# solenoid_valve.net
KiCad netlist of a schematic drawn in EAGLE
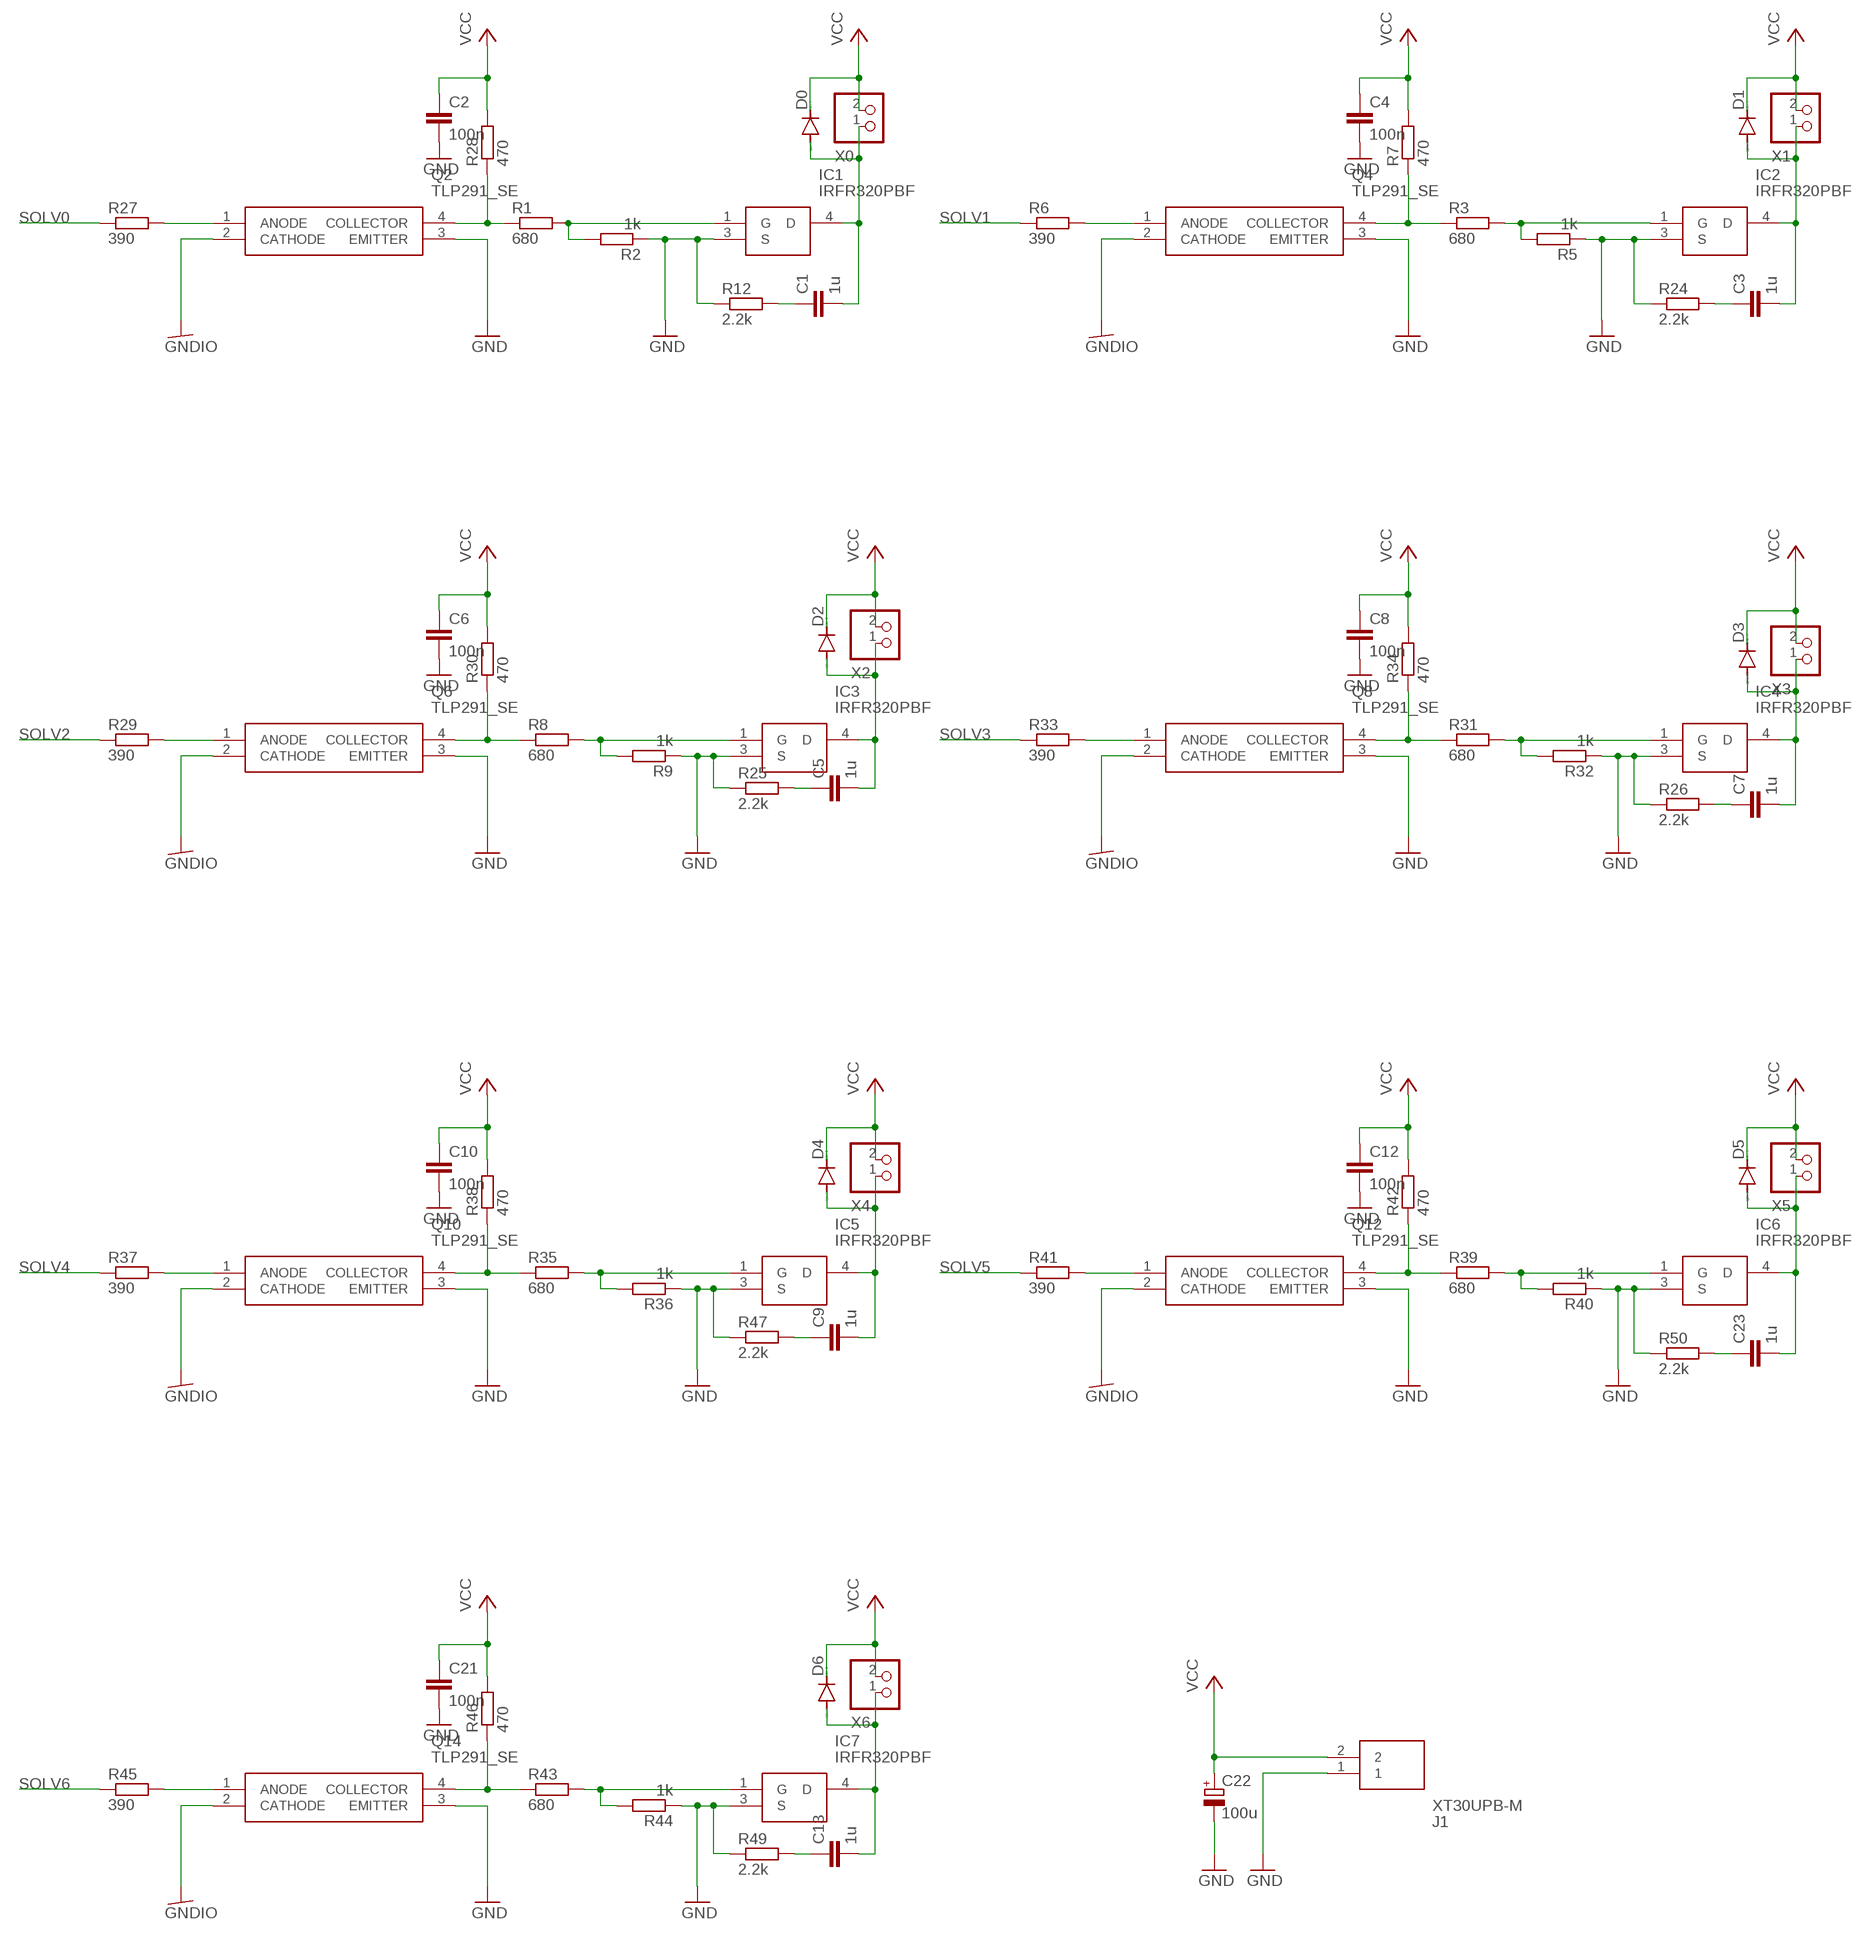
[diagram p0: schematic, sheet 1]
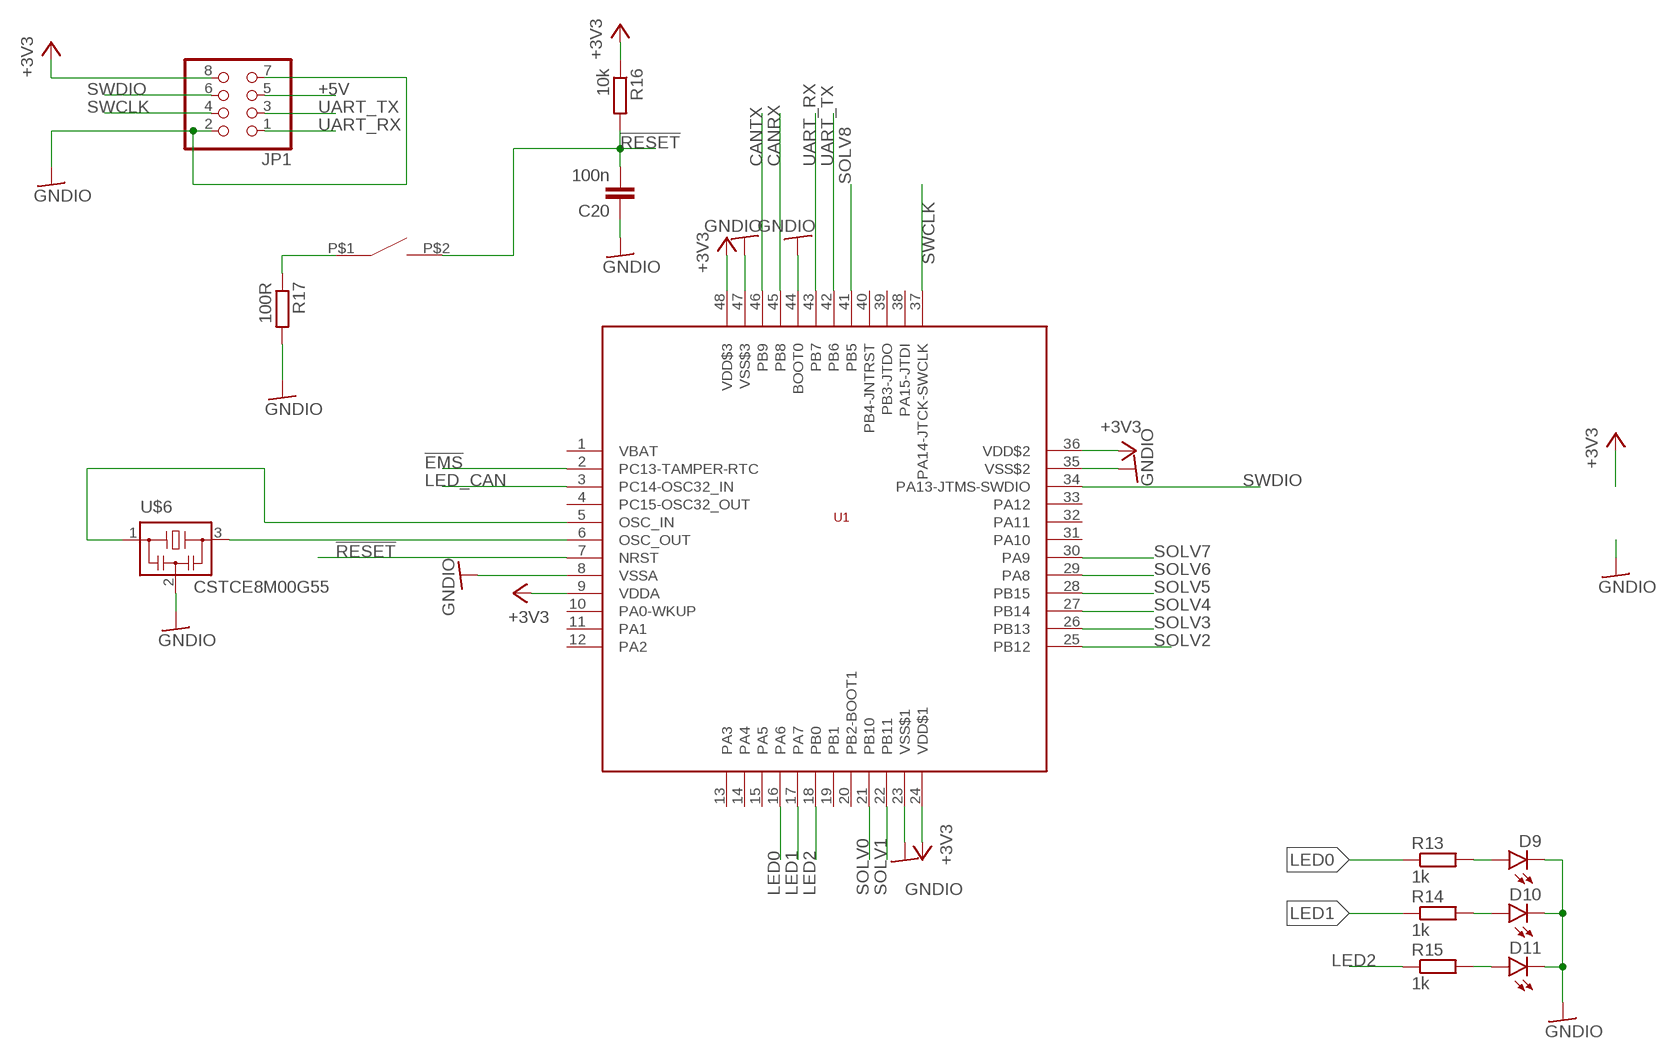
[diagram p1: schematic, sheet 2]
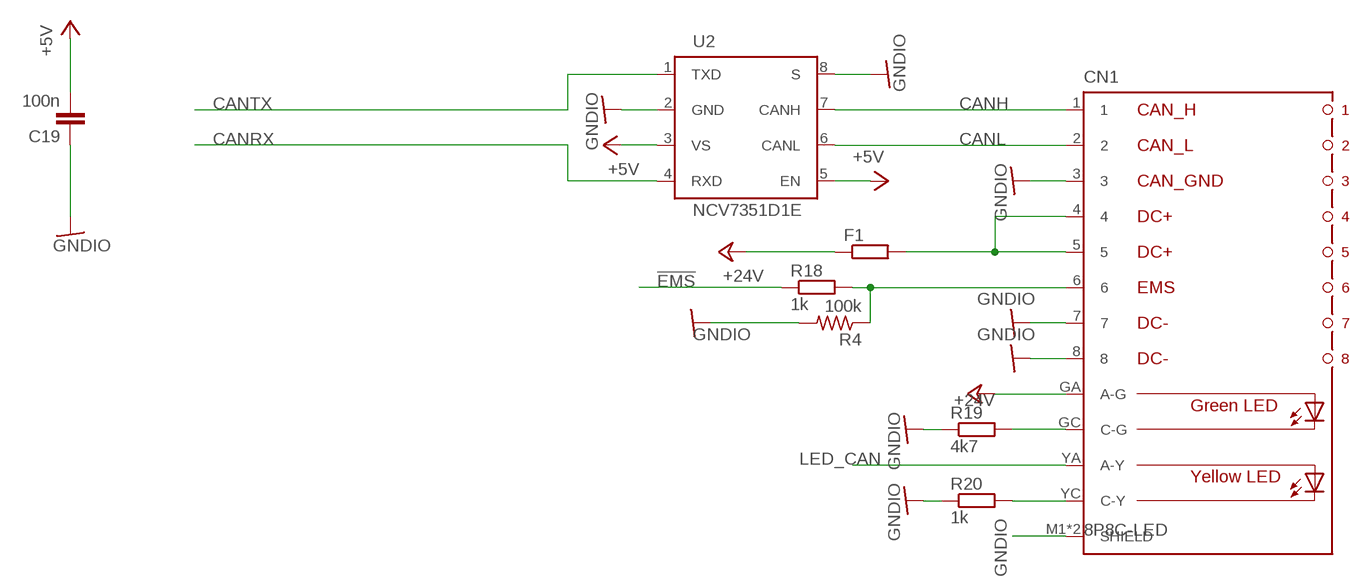
[diagram p2: schematic, sheet 3]
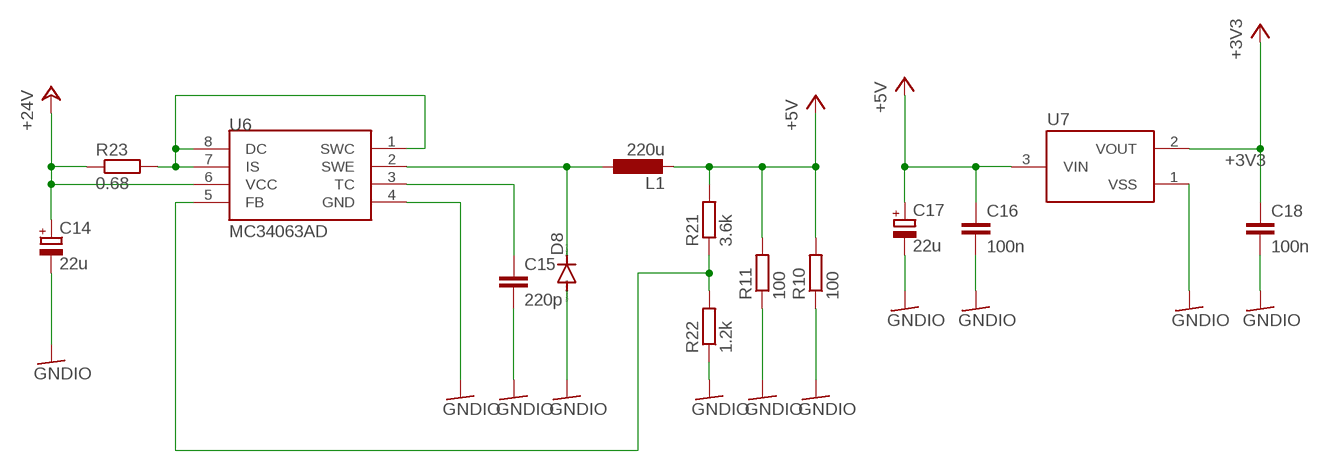
[diagram p3: schematic, sheet 4]

(export (version "E")
  (design (tool "Eeschema 10.0.6"))
  (components
    (comp (ref "C1")
      (value "1u")
      (footprint "eagle-import:C0603")
      (libsource (lib "eagle-import") (part "rcl_334_C-EUC0603"))
    )
    (comp (ref "C2")
      (value "100n")
      (footprint "eagle-import:C0603")
      (libsource (lib "eagle-import") (part "rcl_334_C-EUC0603"))
    )
    (comp (ref "C3")
      (value "1u")
      (footprint "eagle-import:C0603")
      (libsource (lib "eagle-import") (part "rcl_334_C-EUC0603"))
    )
    (comp (ref "C4")
      (value "100n")
      (footprint "eagle-import:C0603")
      (libsource (lib "eagle-import") (part "rcl_334_C-EUC0603"))
    )
    (comp (ref "C5")
      (value "1u")
      (footprint "eagle-import:C0603")
      (libsource (lib "eagle-import") (part "rcl_334_C-EUC0603"))
    )
    (comp (ref "C6")
      (value "100n")
      (footprint "eagle-import:C0603")
      (libsource (lib "eagle-import") (part "rcl_334_C-EUC0603"))
    )
    (comp (ref "C7")
      (value "1u")
      (footprint "eagle-import:C0603")
      (libsource (lib "eagle-import") (part "rcl_334_C-EUC0603"))
    )
    (comp (ref "C8")
      (value "100n")
      (footprint "eagle-import:C0603")
      (libsource (lib "eagle-import") (part "rcl_334_C-EUC0603"))
    )
    (comp (ref "C9")
      (value "1u")
      (footprint "eagle-import:C0603")
      (libsource (lib "eagle-import") (part "rcl_334_C-EUC0603"))
    )
    (comp (ref "C10")
      (value "100n")
      (footprint "eagle-import:C0603")
      (libsource (lib "eagle-import") (part "rcl_334_C-EUC0603"))
    )
    (comp (ref "C12")
      (value "100n")
      (footprint "eagle-import:C0603")
      (libsource (lib "eagle-import") (part "rcl_334_C-EUC0603"))
    )
    (comp (ref "C13")
      (value "1u")
      (footprint "eagle-import:C0603")
      (libsource (lib "eagle-import") (part "rcl_334_C-EUC0603"))
    )
    (comp (ref "C21")
      (value "100n")
      (footprint "eagle-import:C0603")
      (libsource (lib "eagle-import") (part "rcl_334_C-EUC0603"))
    )
    (comp (ref "C22")
      (value "100u")
      (footprint "eagle-import:E2-5")
      (libsource (lib "eagle-import") (part "rcl_334_CPOL-EUE2-5"))
    )
    (comp (ref "C23")
      (value "1u")
      (footprint "eagle-import:C0603")
      (libsource (lib "eagle-import") (part "rcl_334_C-EUC0603"))
    )
    (comp (ref "D0")
      (value "DIODE-SOD123")
      (footprint "eagle-import:SOD123")
      (libsource (lib "eagle-import") (part "DIODE-SOD123"))
    )
    (comp (ref "D1")
      (value "DIODE-SOD123")
      (footprint "eagle-import:SOD123")
      (libsource (lib "eagle-import") (part "DIODE-SOD123"))
    )
    (comp (ref "D2")
      (value "DIODE-SOD123")
      (footprint "eagle-import:SOD123")
      (libsource (lib "eagle-import") (part "DIODE-SOD123"))
    )
    (comp (ref "D3")
      (value "DIODE-SOD123")
      (footprint "eagle-import:SOD123")
      (libsource (lib "eagle-import") (part "DIODE-SOD123"))
    )
    (comp (ref "D4")
      (value "DIODE-SOD123")
      (footprint "eagle-import:SOD123")
      (libsource (lib "eagle-import") (part "DIODE-SOD123"))
    )
    (comp (ref "D5")
      (value "DIODE-SOD123")
      (footprint "eagle-import:SOD123")
      (libsource (lib "eagle-import") (part "DIODE-SOD123"))
    )
    (comp (ref "D6")
      (value "DIODE-SOD123")
      (footprint "eagle-import:SOD123")
      (libsource (lib "eagle-import") (part "DIODE-SOD123"))
    )
    (comp (ref "IC1")
      (value "IRFR320PBF")
      (footprint "eagle-import:TO228P990X238-3N")
      (fields (field (name "MOUSER_PART_NUMBER") "844-IRFR320PBF"))
      (libsource (lib "eagle-import") (part "IRFR320PBF"))
    )
    (comp (ref "IC2")
      (value "IRFR320PBF")
      (footprint "eagle-import:TO228P990X238-3N")
      (fields (field (name "MOUSER_PART_NUMBER") "844-IRFR320PBF"))
      (libsource (lib "eagle-import") (part "IRFR320PBF"))
    )
    (comp (ref "IC3")
      (value "IRFR320PBF")
      (footprint "eagle-import:TO228P990X238-3N")
      (fields (field (name "MOUSER_PART_NUMBER") "844-IRFR320PBF"))
      (libsource (lib "eagle-import") (part "IRFR320PBF"))
    )
    (comp (ref "IC4")
      (value "IRFR320PBF")
      (footprint "eagle-import:TO228P990X238-3N")
      (fields (field (name "MOUSER_PART_NUMBER") "844-IRFR320PBF"))
      (libsource (lib "eagle-import") (part "IRFR320PBF"))
    )
    (comp (ref "IC5")
      (value "IRFR320PBF")
      (footprint "eagle-import:TO228P990X238-3N")
      (fields (field (name "MOUSER_PART_NUMBER") "844-IRFR320PBF"))
      (libsource (lib "eagle-import") (part "IRFR320PBF"))
    )
    (comp (ref "IC6")
      (value "IRFR320PBF")
      (footprint "eagle-import:TO228P990X238-3N")
      (fields (field (name "MOUSER_PART_NUMBER") "844-IRFR320PBF"))
      (libsource (lib "eagle-import") (part "IRFR320PBF"))
    )
    (comp (ref "IC7")
      (value "IRFR320PBF")
      (footprint "eagle-import:TO228P990X238-3N")
      (fields (field (name "MOUSER_PART_NUMBER") "844-IRFR320PBF"))
      (libsource (lib "eagle-import") (part "IRFR320PBF"))
    )
    (comp (ref "J1")
      (value "XT30UPB-M")
      (footprint "eagle-import:SHDR2W160P0X500_1X2_1020X520X1")
      (libsource (lib "eagle-import") (part "XT30UPB-M"))
    )
    (comp (ref "Q2")
      (value "TLP291_SE")
      (footprint "eagle-import:SOIC127P700X230-4N")
      (fields
        (field (name "ARROW_PART_NUMBER") "TLP291(SE")
        (field (name "MOUSER_PART_NUMBER") "757-TLP291SE")
      )
      (libsource (lib "eagle-import") (part "TLP291_SE"))
    )
    (comp (ref "Q4")
      (value "TLP291_SE")
      (footprint "eagle-import:SOIC127P700X230-4N")
      (fields
        (field (name "ARROW_PART_NUMBER") "TLP291(SE")
        (field (name "MOUSER_PART_NUMBER") "757-TLP291SE")
      )
      (libsource (lib "eagle-import") (part "TLP291_SE"))
    )
    (comp (ref "Q6")
      (value "TLP291_SE")
      (footprint "eagle-import:SOIC127P700X230-4N")
      (fields
        (field (name "ARROW_PART_NUMBER") "TLP291(SE")
        (field (name "MOUSER_PART_NUMBER") "757-TLP291SE")
      )
      (libsource (lib "eagle-import") (part "TLP291_SE"))
    )
    (comp (ref "Q8")
      (value "TLP291_SE")
      (footprint "eagle-import:SOIC127P700X230-4N")
      (fields
        (field (name "ARROW_PART_NUMBER") "TLP291(SE")
        (field (name "MOUSER_PART_NUMBER") "757-TLP291SE")
      )
      (libsource (lib "eagle-import") (part "TLP291_SE"))
    )
    (comp (ref "Q10")
      (value "TLP291_SE")
      (footprint "eagle-import:SOIC127P700X230-4N")
      (fields
        (field (name "ARROW_PART_NUMBER") "TLP291(SE")
        (field (name "MOUSER_PART_NUMBER") "757-TLP291SE")
      )
      (libsource (lib "eagle-import") (part "TLP291_SE"))
    )
    (comp (ref "Q12")
      (value "TLP291_SE")
      (footprint "eagle-import:SOIC127P700X230-4N")
      (fields
        (field (name "ARROW_PART_NUMBER") "TLP291(SE")
        (field (name "MOUSER_PART_NUMBER") "757-TLP291SE")
      )
      (libsource (lib "eagle-import") (part "TLP291_SE"))
    )
    (comp (ref "Q14")
      (value "TLP291_SE")
      (footprint "eagle-import:SOIC127P700X230-4N")
      (fields
        (field (name "ARROW_PART_NUMBER") "TLP291(SE")
        (field (name "MOUSER_PART_NUMBER") "757-TLP291SE")
      )
      (libsource (lib "eagle-import") (part "TLP291_SE"))
    )
    (comp (ref "R1")
      (value "680")
      (footprint "eagle-import:R0603")
      (libsource (lib "eagle-import") (part "rcl_334_R-EU_R0603"))
    )
    (comp (ref "R2")
      (value "1k")
      (footprint "eagle-import:R0603")
      (libsource (lib "eagle-import") (part "rcl_334_R-EU_R0603"))
    )
    (comp (ref "R3")
      (value "680")
      (footprint "eagle-import:R0603")
      (libsource (lib "eagle-import") (part "rcl_334_R-EU_R0603"))
    )
    (comp (ref "R5")
      (value "1k")
      (footprint "eagle-import:R0603")
      (libsource (lib "eagle-import") (part "rcl_334_R-EU_R0603"))
    )
    (comp (ref "R6")
      (value "390")
      (footprint "eagle-import:R0603")
      (libsource (lib "eagle-import") (part "rcl_334_R-EU_R0603"))
    )
    (comp (ref "R7")
      (value "470")
      (footprint "eagle-import:R0603")
      (libsource (lib "eagle-import") (part "rcl_334_R-EU_R0603"))
    )
    (comp (ref "R8")
      (value "680")
      (footprint "eagle-import:R0603")
      (libsource (lib "eagle-import") (part "rcl_334_R-EU_R0603"))
    )
    (comp (ref "R9")
      (value "1k")
      (footprint "eagle-import:R0603")
      (libsource (lib "eagle-import") (part "rcl_334_R-EU_R0603"))
    )
    (comp (ref "R12")
      (value "2.2k")
      (footprint "eagle-import:R0603")
      (libsource (lib "eagle-import") (part "rcl_334_R-EU_R0603"))
    )
    (comp (ref "R24")
      (value "2.2k")
      (footprint "eagle-import:R0603")
      (libsource (lib "eagle-import") (part "rcl_334_R-EU_R0603"))
    )
    (comp (ref "R25")
      (value "2.2k")
      (footprint "eagle-import:R0603")
      (libsource (lib "eagle-import") (part "rcl_334_R-EU_R0603"))
    )
    (comp (ref "R26")
      (value "2.2k")
      (footprint "eagle-import:R0603")
      (libsource (lib "eagle-import") (part "rcl_334_R-EU_R0603"))
    )
    (comp (ref "R27")
      (value "390")
      (footprint "eagle-import:R0603")
      (libsource (lib "eagle-import") (part "rcl_334_R-EU_R0603"))
    )
    (comp (ref "R28")
      (value "470")
      (footprint "eagle-import:R0603")
      (libsource (lib "eagle-import") (part "rcl_334_R-EU_R0603"))
    )
    (comp (ref "R29")
      (value "390")
      (footprint "eagle-import:R0603")
      (libsource (lib "eagle-import") (part "rcl_334_R-EU_R0603"))
    )
    (comp (ref "R30")
      (value "470")
      (footprint "eagle-import:R0603")
      (libsource (lib "eagle-import") (part "rcl_334_R-EU_R0603"))
    )
    (comp (ref "R31")
      (value "680")
      (footprint "eagle-import:R0603")
      (libsource (lib "eagle-import") (part "rcl_334_R-EU_R0603"))
    )
    (comp (ref "R32")
      (value "1k")
      (footprint "eagle-import:R0603")
      (libsource (lib "eagle-import") (part "rcl_334_R-EU_R0603"))
    )
    (comp (ref "R33")
      (value "390")
      (footprint "eagle-import:R0603")
      (libsource (lib "eagle-import") (part "rcl_334_R-EU_R0603"))
    )
    (comp (ref "R34")
      (value "470")
      (footprint "eagle-import:R0603")
      (libsource (lib "eagle-import") (part "rcl_334_R-EU_R0603"))
    )
    (comp (ref "R35")
      (value "680")
      (footprint "eagle-import:R0603")
      (libsource (lib "eagle-import") (part "rcl_334_R-EU_R0603"))
    )
    (comp (ref "R36")
      (value "1k")
      (footprint "eagle-import:R0603")
      (libsource (lib "eagle-import") (part "rcl_334_R-EU_R0603"))
    )
    (comp (ref "R37")
      (value "390")
      (footprint "eagle-import:R0603")
      (libsource (lib "eagle-import") (part "rcl_334_R-EU_R0603"))
    )
    (comp (ref "R38")
      (value "470")
      (footprint "eagle-import:R0603")
      (libsource (lib "eagle-import") (part "rcl_334_R-EU_R0603"))
    )
    (comp (ref "R39")
      (value "680")
      (footprint "eagle-import:R0603")
      (libsource (lib "eagle-import") (part "rcl_334_R-EU_R0603"))
    )
    (comp (ref "R40")
      (value "1k")
      (footprint "eagle-import:R0603")
      (libsource (lib "eagle-import") (part "rcl_334_R-EU_R0603"))
    )
    (comp (ref "R41")
      (value "390")
      (footprint "eagle-import:R0603")
      (libsource (lib "eagle-import") (part "rcl_334_R-EU_R0603"))
    )
    (comp (ref "R42")
      (value "470")
      (footprint "eagle-import:R0603")
      (libsource (lib "eagle-import") (part "rcl_334_R-EU_R0603"))
    )
    (comp (ref "R43")
      (value "680")
      (footprint "eagle-import:R0603")
      (libsource (lib "eagle-import") (part "rcl_334_R-EU_R0603"))
    )
    (comp (ref "R44")
      (value "1k")
      (footprint "eagle-import:R0603")
      (libsource (lib "eagle-import") (part "rcl_334_R-EU_R0603"))
    )
    (comp (ref "R45")
      (value "390")
      (footprint "eagle-import:R0603")
      (libsource (lib "eagle-import") (part "rcl_334_R-EU_R0603"))
    )
    (comp (ref "R46")
      (value "470")
      (footprint "eagle-import:R0603")
      (libsource (lib "eagle-import") (part "rcl_334_R-EU_R0603"))
    )
    (comp (ref "R47")
      (value "2.2k")
      (footprint "eagle-import:R0603")
      (libsource (lib "eagle-import") (part "rcl_334_R-EU_R0603"))
    )
    (comp (ref "R49")
      (value "2.2k")
      (footprint "eagle-import:R0603")
      (libsource (lib "eagle-import") (part "rcl_334_R-EU_R0603"))
    )
    (comp (ref "R50")
      (value "2.2k")
      (footprint "eagle-import:R0603")
      (libsource (lib "eagle-import") (part "rcl_334_R-EU_R0603"))
    )
    (comp (ref "X0")
      (value "S2B-XASK-1")
      (footprint "eagle-import:S2B-XASK-1")
      (libsource (lib "eagle-import") (part "S2B-XASK-1"))
    )
    (comp (ref "X1")
      (value "S2B-XASK-1")
      (footprint "eagle-import:S2B-XASK-1")
      (libsource (lib "eagle-import") (part "S2B-XASK-1"))
    )
    (comp (ref "X2")
      (value "S2B-XASK-1")
      (footprint "eagle-import:S2B-XASK-1")
      (libsource (lib "eagle-import") (part "S2B-XASK-1"))
    )
    (comp (ref "X3")
      (value "S2B-XASK-1")
      (footprint "eagle-import:S2B-XASK-1")
      (libsource (lib "eagle-import") (part "S2B-XASK-1"))
    )
    (comp (ref "X4")
      (value "S2B-XASK-1")
      (footprint "eagle-import:S2B-XASK-1")
      (libsource (lib "eagle-import") (part "S2B-XASK-1"))
    )
    (comp (ref "X5")
      (value "S2B-XASK-1")
      (footprint "eagle-import:S2B-XASK-1")
      (libsource (lib "eagle-import") (part "S2B-XASK-1"))
    )
    (comp (ref "X6")
      (value "S2B-XASK-1")
      (footprint "eagle-import:S2B-XASK-1")
      (libsource (lib "eagle-import") (part "S2B-XASK-1"))
    )
    (comp (ref "C14")
      (value "22u")
      (footprint "eagle-import:E2-5")
      (libsource (lib "eagle-import") (part "CPOL-EUE2-5"))
    )
    (comp (ref "C15")
      (value "220p")
      (footprint "eagle-import:C0603")
      (libsource (lib "eagle-import") (part "rcl_334_C-EUC0603"))
    )
    (comp (ref "C16")
      (value "100n")
      (footprint "eagle-import:C0603")
      (libsource (lib "eagle-import") (part "C-EUC0603"))
    )
    (comp (ref "C17")
      (value "22u")
      (footprint "eagle-import:E2-5")
      (libsource (lib "eagle-import") (part "CPOL-EUE2-5"))
    )
    (comp (ref "C18")
      (value "100n")
      (footprint "eagle-import:C0603")
      (libsource (lib "eagle-import") (part "C-EUC0603"))
    )
    (comp (ref "D8")
      (value "DIODE-SOD123")
      (footprint "eagle-import:SOD123")
      (libsource (lib "eagle-import") (part "DIODE-SOD123"))
    )
    (comp (ref "L1")
      (value "220u")
      (footprint "eagle-import:L5852")
      (libsource (lib "eagle-import") (part "L5852"))
    )
    (comp (ref "R10")
      (value "100")
      (footprint "eagle-import:R0603")
      (libsource (lib "eagle-import") (part "rcl_334_R-EU_R0603"))
    )
    (comp (ref "R11")
      (value "100")
      (footprint "eagle-import:R0603")
      (libsource (lib "eagle-import") (part "rcl_334_R-EU_R0603"))
    )
    (comp (ref "R21")
      (value "3.6k")
      (footprint "eagle-import:R0603")
      (libsource (lib "eagle-import") (part "rcl_334_R-EU_R0603"))
    )
    (comp (ref "R22")
      (value "1.2k")
      (footprint "eagle-import:R0603")
      (libsource (lib "eagle-import") (part "rcl_334_R-EU_R0603"))
    )
    (comp (ref "R23")
      (value "0.68")
      (footprint "eagle-import:R1206")
      (libsource (lib "eagle-import") (part "rcl_334_R-EU_R1206"))
    )
    (comp (ref "U6")
      (value "MC34063AD")
      (footprint "eagle-import:SOIC8")
      (libsource (lib "eagle-import") (part "MC34063AD"))
    )
    (comp (ref "U7")
      (value "XC6206")
      (footprint "eagle-import:SOT95P240X110-3")
      (libsource (lib "eagle-import") (part "XC6206"))
    )
    (comp (ref "C20")
      (value "100n")
      (footprint "eagle-import:C0603")
      (libsource (lib "eagle-import") (part "C-EUC0603"))
    )
    (comp (ref "D9")
      (value "LEDCHIPLED_0805")
      (footprint "eagle-import:CHIPLED_0805")
      (libsource (lib "eagle-import") (part "LEDCHIPLED_0805"))
    )
    (comp (ref "D10")
      (value "LEDCHIPLED_0805")
      (footprint "eagle-import:CHIPLED_0805")
      (libsource (lib "eagle-import") (part "LEDCHIPLED_0805"))
    )
    (comp (ref "D11")
      (value "LEDCHIPLED_0805")
      (footprint "eagle-import:CHIPLED_0805")
      (libsource (lib "eagle-import") (part "LEDCHIPLED_0805"))
    )
    (comp (ref "JP1")
      (value "PINHD-2X4")
      (footprint "eagle-import:2X04")
      (libsource (lib "eagle-import") (part "PINHD-2X4"))
    )
    (comp (ref "R13")
      (value "1k")
      (footprint "eagle-import:R0603")
      (libsource (lib "eagle-import") (part "R-EU_R0603"))
    )
    (comp (ref "R14")
      (value "1k")
      (footprint "eagle-import:R0603")
      (libsource (lib "eagle-import") (part "R-EU_R0603"))
    )
    (comp (ref "R15")
      (value "1k")
      (footprint "eagle-import:R0603")
      (libsource (lib "eagle-import") (part "R-EU_R0603"))
    )
    (comp (ref "R16")
      (value "10k")
      (footprint "eagle-import:R0603")
      (libsource (lib "eagle-import") (part "R-EU_R0603"))
    )
    (comp (ref "R17")
      (value "100R")
      (footprint "eagle-import:R0603")
      (libsource (lib "eagle-import") (part "R-EU_R0603"))
    )
    (comp (ref "SW1")
      (value "SWITCH_TACTILETOP")
      (footprint "eagle-import:SWITCH_TACTILE_3X6")
      (libsource (lib "eagle-import") (part "SWITCH_TACTILETOP"))
    )
    (comp (ref "U$6")
      (value "CSTCE8M00G55")
      (footprint "eagle-import:CSTCE8M00G55")
      (libsource (lib "eagle-import") (part "CSTCE8M00G55"))
    )
    (comp (ref "U1")
      (value "STM32F103C8")
      (footprint "eagle-import:LQFP48")
      (libsource (lib "eagle-import") (part "STM32F103C8"))
    )
    (comp (ref "C19")
      (value "100n")
      (footprint "eagle-import:C0603")
      (libsource (lib "eagle-import") (part "C-EUC0603"))
    )
    (comp (ref "CN1")
      (value "8P8C-LED")
      (footprint "eagle-import:8P8C-LED")
      (libsource (lib "eagle-import") (part "8P8C-LED"))
    )
    (comp (ref "F1")
      (value "R-EU_R1206")
      (footprint "eagle-import:R1206")
      (libsource (lib "eagle-import") (part "rcl_334_R-EU_R1206"))
    )
    (comp (ref "R4")
      (value "100k")
      (footprint "eagle-import:R0603")
      (libsource (lib "eagle-import") (part "R-US_R0603"))
    )
    (comp (ref "R18")
      (value "1k")
      (footprint "eagle-import:R0603")
      (libsource (lib "eagle-import") (part "rcl_334_R-EU_R0603"))
    )
    (comp (ref "R19")
      (value "4k7")
      (footprint "eagle-import:R0603")
      (libsource (lib "eagle-import") (part "rcl_334_R-EU_R0603"))
    )
    (comp (ref "R20")
      (value "1k")
      (footprint "eagle-import:R0603")
      (libsource (lib "eagle-import") (part "rcl_334_R-EU_R0603"))
    )
    (comp (ref "U2")
      (value "NCV7351D1E")
      (footprint "eagle-import:SO08")
      (libsource (lib "eagle-import") (part "NCV7351D1E"))
    )
  )
  (nets
    (net (code "1") (name "+3V3") (class "Default")
      (node (ref "C18") (pin "1") (pinfunction "1_1") (pintype "passive"))
      (node (ref "JP1") (pin "8") (pinfunction "8_8") (pintype "passive"))
      (node (ref "R16") (pin "1") (pinfunction "1_1") (pintype "passive"))
      (node (ref "U1") (pin "24") (pinfunction "VDD$1_24") (pintype "passive"))
      (node (ref "U1") (pin "36") (pinfunction "VDD$2_36") (pintype "passive"))
      (node (ref "U1") (pin "48") (pinfunction "VDD$3_48") (pintype "passive"))
      (node (ref "U1") (pin "9") (pinfunction "VDDA_9") (pintype "bidirectional"))
      (node (ref "U7") (pin "2") (pinfunction "VOUT_2") (pintype "bidirectional"))
    )
    (net (code "2") (name "+5V") (class "Default")
      (node (ref "C16") (pin "1") (pinfunction "1_1") (pintype "passive"))
      (node (ref "C17") (pin "+") (pinfunction "+_+") (pintype "passive"))
      (node (ref "C19") (pin "2") (pinfunction "2_2") (pintype "passive"))
      (node (ref "JP1") (pin "5") (pinfunction "5_5") (pintype "passive"))
      (node (ref "L1") (pin "P$2") (pinfunction "2_P$2") (pintype "passive"))
      (node (ref "R10") (pin "2") (pinfunction "2_2") (pintype "passive"))
      (node (ref "R11") (pin "2") (pinfunction "2_2") (pintype "passive"))
      (node (ref "R21") (pin "2") (pinfunction "2_2") (pintype "passive"))
      (node (ref "U2") (pin "3") (pinfunction "VS_3") (pintype "power_in"))
      (node (ref "U2") (pin "5") (pinfunction "EN_5") (pintype "input"))
      (node (ref "U7") (pin "3") (pinfunction "VIN_3") (pintype "bidirectional"))
    )
    (net (code "3") (name "+24V") (class "Default")
      (node (ref "C14") (pin "+") (pinfunction "+_+") (pintype "passive"))
      (node (ref "CN1") (pin "GA") (pinfunction "A-G_GA") (pintype "passive"))
      (node (ref "F1") (pin "1") (pinfunction "1_1") (pintype "passive"))
      (node (ref "R23") (pin "1") (pinfunction "1_1") (pintype "passive"))
      (node (ref "U6") (pin "6") (pinfunction "VCC_6") (pintype "passive"))
    )
    (net (code "4") (name "CANH") (class "Default")
      (node (ref "CN1") (pin "1") (pinfunction "1_1") (pintype "input"))
      (node (ref "U2") (pin "7") (pinfunction "CANH_7") (pintype "output"))
    )
    (net (code "5") (name "CANL") (class "Default")
      (node (ref "CN1") (pin "2") (pinfunction "2_2") (pintype "input"))
      (node (ref "U2") (pin "6") (pinfunction "CANL_6") (pintype "output"))
    )
    (net (code "6") (name "CANRX") (class "Default")
      (node (ref "U1") (pin "45") (pinfunction "PB8_45") (pintype "bidirectional"))
      (node (ref "U2") (pin "4") (pinfunction "RXD_4") (pintype "output"))
    )
    (net (code "7") (name "CANTX") (class "Default")
      (node (ref "U1") (pin "46") (pinfunction "PB9_46") (pintype "bidirectional"))
      (node (ref "U2") (pin "1") (pinfunction "TXD_1") (pintype "input"))
    )
    (net (code "8") (name "GND") (class "Default")
      (node (ref "C10") (pin "2") (pinfunction "2_2") (pintype "passive"))
      (node (ref "C12") (pin "2") (pinfunction "2_2") (pintype "passive"))
      (node (ref "C2") (pin "2") (pinfunction "2_2") (pintype "passive"))
      (node (ref "C21") (pin "2") (pinfunction "2_2") (pintype "passive"))
      (node (ref "C22") (pin "-") (pinfunction "-_-") (pintype "passive"))
      (node (ref "C4") (pin "2") (pinfunction "2_2") (pintype "passive"))
      (node (ref "C6") (pin "2") (pinfunction "2_2") (pintype "passive"))
      (node (ref "C8") (pin "2") (pinfunction "2_2") (pintype "passive"))
      (node (ref "IC1") (pin "3") (pinfunction "S_3") (pintype "bidirectional"))
      (node (ref "IC2") (pin "3") (pinfunction "S_3") (pintype "bidirectional"))
      (node (ref "IC3") (pin "3") (pinfunction "S_3") (pintype "bidirectional"))
      (node (ref "IC4") (pin "3") (pinfunction "S_3") (pintype "bidirectional"))
      (node (ref "IC5") (pin "3") (pinfunction "S_3") (pintype "bidirectional"))
      (node (ref "IC6") (pin "3") (pinfunction "S_3") (pintype "bidirectional"))
      (node (ref "IC7") (pin "3") (pinfunction "S_3") (pintype "bidirectional"))
      (node (ref "J1") (pin "1") (pinfunction "1_1") (pintype "bidirectional"))
      (node (ref "Q10") (pin "3") (pinfunction "EMITTER_3") (pintype "bidirectional"))
      (node (ref "Q12") (pin "3") (pinfunction "EMITTER_3") (pintype "bidirectional"))
      (node (ref "Q14") (pin "3") (pinfunction "EMITTER_3") (pintype "bidirectional"))
      (node (ref "Q2") (pin "3") (pinfunction "EMITTER_3") (pintype "bidirectional"))
      (node (ref "Q4") (pin "3") (pinfunction "EMITTER_3") (pintype "bidirectional"))
      (node (ref "Q6") (pin "3") (pinfunction "EMITTER_3") (pintype "bidirectional"))
      (node (ref "Q8") (pin "3") (pinfunction "EMITTER_3") (pintype "bidirectional"))
      (node (ref "R12") (pin "1") (pinfunction "1_1") (pintype "passive"))
      (node (ref "R2") (pin "1") (pinfunction "1_1") (pintype "passive"))
      (node (ref "R24") (pin "1") (pinfunction "1_1") (pintype "passive"))
      (node (ref "R25") (pin "1") (pinfunction "1_1") (pintype "passive"))
      (node (ref "R26") (pin "1") (pinfunction "1_1") (pintype "passive"))
      (node (ref "R32") (pin "1") (pinfunction "1_1") (pintype "passive"))
      (node (ref "R36") (pin "1") (pinfunction "1_1") (pintype "passive"))
      (node (ref "R40") (pin "1") (pinfunction "1_1") (pintype "passive"))
      (node (ref "R44") (pin "1") (pinfunction "1_1") (pintype "passive"))
      (node (ref "R47") (pin "1") (pinfunction "1_1") (pintype "passive"))
      (node (ref "R49") (pin "1") (pinfunction "1_1") (pintype "passive"))
      (node (ref "R5") (pin "1") (pinfunction "1_1") (pintype "passive"))
      (node (ref "R50") (pin "1") (pinfunction "1_1") (pintype "passive"))
      (node (ref "R9") (pin "1") (pinfunction "1_1") (pintype "passive"))
    )
    (net (code "9") (name "GNDIO") (class "Default")
      (node (ref "C14") (pin "-") (pinfunction "-_-") (pintype "passive"))
      (node (ref "C15") (pin "2") (pinfunction "2_2") (pintype "passive"))
      (node (ref "C16") (pin "2") (pinfunction "2_2") (pintype "passive"))
      (node (ref "C17") (pin "-") (pinfunction "-_-") (pintype "passive"))
      (node (ref "C18") (pin "2") (pinfunction "2_2") (pintype "passive"))
      (node (ref "C19") (pin "1") (pinfunction "1_1") (pintype "passive"))
      (node (ref "C20") (pin "1") (pinfunction "1_1") (pintype "passive"))
      (node (ref "CN1") (pin "3") (pinfunction "3_3") (pintype "input"))
      (node (ref "CN1") (pin "7") (pinfunction "7_7") (pintype "input"))
      (node (ref "CN1") (pin "8") (pinfunction "8_8") (pintype "input"))
      (node (ref "CN1") (pin "M1") (pinfunction "SHIELD_M1") (pintype "passive"))
      (node (ref "CN1") (pin "M2") (pinfunction "SHIELD_M2") (pintype "passive"))
      (node (ref "D10") (pin "C") (pinfunction "C_C") (pintype "passive"))
      (node (ref "D11") (pin "C") (pinfunction "C_C") (pintype "passive"))
      (node (ref "D8") (pin "A") (pinfunction "A_A") (pintype "passive"))
      (node (ref "D9") (pin "C") (pinfunction "C_C") (pintype "passive"))
      (node (ref "JP1") (pin "2") (pinfunction "2_2") (pintype "passive"))
      (node (ref "JP1") (pin "7") (pinfunction "7_7") (pintype "passive"))
      (node (ref "Q10") (pin "2") (pinfunction "CATHODE_2") (pintype "bidirectional"))
      (node (ref "Q12") (pin "2") (pinfunction "CATHODE_2") (pintype "bidirectional"))
      (node (ref "Q14") (pin "2") (pinfunction "CATHODE_2") (pintype "bidirectional"))
      (node (ref "Q2") (pin "2") (pinfunction "CATHODE_2") (pintype "bidirectional"))
      (node (ref "Q4") (pin "2") (pinfunction "CATHODE_2") (pintype "bidirectional"))
      (node (ref "Q6") (pin "2") (pinfunction "CATHODE_2") (pintype "bidirectional"))
      (node (ref "Q8") (pin "2") (pinfunction "CATHODE_2") (pintype "bidirectional"))
      (node (ref "R10") (pin "1") (pinfunction "1_1") (pintype "passive"))
      (node (ref "R11") (pin "1") (pinfunction "1_1") (pintype "passive"))
      (node (ref "R17") (pin "2") (pinfunction "2_2") (pintype "passive"))
      (node (ref "R19") (pin "1") (pinfunction "1_1") (pintype "passive"))
      (node (ref "R20") (pin "1") (pinfunction "1_1") (pintype "passive"))
      (node (ref "R22") (pin "1") (pinfunction "1_1") (pintype "passive"))
      (node (ref "R4") (pin "2") (pinfunction "2_2") (pintype "passive"))
      (node (ref "U$6") (pin "2") (pinfunction "2_2") (pintype "passive"))
      (node (ref "U1") (pin "23") (pinfunction "VSS$1_23") (pintype "passive"))
      (node (ref "U1") (pin "35") (pinfunction "VSS$2_35") (pintype "passive"))
      (node (ref "U1") (pin "44") (pinfunction "BOOT0_44") (pintype "input"))
      (node (ref "U1") (pin "47") (pinfunction "VSS$3_47") (pintype "passive"))
      (node (ref "U1") (pin "8") (pinfunction "VSSA_8") (pintype "bidirectional"))
      (node (ref "U2") (pin "2") (pinfunction "GND_2") (pintype "power_in"))
      (node (ref "U2") (pin "8") (pinfunction "S_8") (pintype "input"))
      (node (ref "U6") (pin "4") (pinfunction "GND_4") (pintype "passive"))
      (node (ref "U7") (pin "1") (pinfunction "VSS_1") (pintype "bidirectional"))
    )
    (net (code "10") (name "LED0") (class "Default")
      (node (ref "R13") (pin "1") (pinfunction "1_1") (pintype "passive"))
      (node (ref "U1") (pin "16") (pinfunction "PA6_16") (pintype "bidirectional"))
    )
    (net (code "11") (name "LED1") (class "Default")
      (node (ref "R14") (pin "1") (pinfunction "1_1") (pintype "passive"))
      (node (ref "U1") (pin "17") (pinfunction "PA7_17") (pintype "bidirectional"))
    )
    (net (code "12") (name "LED2") (class "Default")
      (node (ref "R15") (pin "1") (pinfunction "1_1") (pintype "passive"))
      (node (ref "U1") (pin "18") (pinfunction "PB0_18") (pintype "bidirectional"))
    )
    (net (code "13") (name "LED_CAN") (class "Default")
      (node (ref "CN1") (pin "YA") (pinfunction "A-Y_YA") (pintype "passive"))
      (node (ref "U1") (pin "3") (pinfunction "PC14-OSC32_IN_3") (pintype "bidirectional"))
    )
    (net (code "14") (name "Net-(C1-Pad1)") (class "Default")
      (node (ref "C1") (pin "1") (pinfunction "1_1") (pintype "passive"))
      (node (ref "R12") (pin "2") (pinfunction "2_2") (pintype "passive"))
    )
    (net (code "15") (name "Net-(C3-Pad1)") (class "Default")
      (node (ref "C3") (pin "1") (pinfunction "1_1") (pintype "passive"))
      (node (ref "R24") (pin "2") (pinfunction "2_2") (pintype "passive"))
    )
    (net (code "16") (name "Net-(C5-Pad1)") (class "Default")
      (node (ref "C5") (pin "1") (pinfunction "1_1") (pintype "passive"))
      (node (ref "R25") (pin "2") (pinfunction "2_2") (pintype "passive"))
    )
    (net (code "17") (name "Net-(C7-Pad1)") (class "Default")
      (node (ref "C7") (pin "1") (pinfunction "1_1") (pintype "passive"))
      (node (ref "R26") (pin "2") (pinfunction "2_2") (pintype "passive"))
    )
    (net (code "18") (name "Net-(C9-Pad1)") (class "Default")
      (node (ref "C9") (pin "1") (pinfunction "1_1") (pintype "passive"))
      (node (ref "R47") (pin "2") (pinfunction "2_2") (pintype "passive"))
    )
    (net (code "19") (name "Net-(C13-Pad1)") (class "Default")
      (node (ref "C13") (pin "1") (pinfunction "1_1") (pintype "passive"))
      (node (ref "R49") (pin "2") (pinfunction "2_2") (pintype "passive"))
    )
    (net (code "20") (name "Net-(C23-Pad1)") (class "Default")
      (node (ref "C23") (pin "1") (pinfunction "1_1") (pintype "passive"))
      (node (ref "R50") (pin "2") (pinfunction "2_2") (pintype "passive"))
    )
    (net (code "21") (name "Net-(CN1-C-G)") (class "Default")
      (node (ref "CN1") (pin "GC") (pinfunction "C-G_GC") (pintype "passive"))
      (node (ref "R19") (pin "2") (pinfunction "2_2") (pintype "passive"))
    )
    (net (code "22") (name "Net-(CN1-C-Y)") (class "Default")
      (node (ref "CN1") (pin "YC") (pinfunction "C-Y_YC") (pintype "passive"))
      (node (ref "R20") (pin "2") (pinfunction "2_2") (pintype "passive"))
    )
    (net (code "23") (name "Net-(CN1-Pad4)") (class "Default")
      (node (ref "CN1") (pin "4") (pinfunction "4_4") (pintype "input"))
      (node (ref "CN1") (pin "5") (pinfunction "5_5") (pintype "input"))
      (node (ref "F1") (pin "2") (pinfunction "2_2") (pintype "passive"))
    )
    (net (code "24") (name "Net-(CN1-Pad6)") (class "Default")
      (node (ref "CN1") (pin "6") (pinfunction "6_6") (pintype "input"))
      (node (ref "R18") (pin "2") (pinfunction "2_2") (pintype "passive"))
      (node (ref "R4") (pin "1") (pinfunction "1_1") (pintype "passive"))
    )
    (net (code "25") (name "Net-(D9-PadA)") (class "Default")
      (node (ref "D9") (pin "A") (pinfunction "A_A") (pintype "passive"))
      (node (ref "R13") (pin "2") (pinfunction "2_2") (pintype "passive"))
    )
    (net (code "26") (name "Net-(D10-PadA)") (class "Default")
      (node (ref "D10") (pin "A") (pinfunction "A_A") (pintype "passive"))
      (node (ref "R14") (pin "2") (pinfunction "2_2") (pintype "passive"))
    )
    (net (code "27") (name "Net-(D11-PadA)") (class "Default")
      (node (ref "D11") (pin "A") (pinfunction "A_A") (pintype "passive"))
      (node (ref "R15") (pin "2") (pinfunction "2_2") (pintype "passive"))
    )
    (net (code "28") (name "Net-(IC1-D)") (class "Default")
      (node (ref "C1") (pin "2") (pinfunction "2_2") (pintype "passive"))
      (node (ref "D0") (pin "A") (pinfunction "A_A") (pintype "passive"))
      (node (ref "IC1") (pin "4") (pinfunction "D_4") (pintype "bidirectional"))
      (node (ref "X0") (pin "1") (pinfunction "1_1") (pintype "passive"))
    )
    (net (code "29") (name "Net-(IC1-G)") (class "Default")
      (node (ref "IC1") (pin "1") (pinfunction "G_1") (pintype "bidirectional"))
      (node (ref "R1") (pin "2") (pinfunction "2_2") (pintype "passive"))
      (node (ref "R2") (pin "2") (pinfunction "2_2") (pintype "passive"))
    )
    (net (code "30") (name "Net-(IC2-D)") (class "Default")
      (node (ref "C3") (pin "2") (pinfunction "2_2") (pintype "passive"))
      (node (ref "D1") (pin "A") (pinfunction "A_A") (pintype "passive"))
      (node (ref "IC2") (pin "4") (pinfunction "D_4") (pintype "bidirectional"))
      (node (ref "X1") (pin "1") (pinfunction "1_1") (pintype "passive"))
    )
    (net (code "31") (name "Net-(IC2-G)") (class "Default")
      (node (ref "IC2") (pin "1") (pinfunction "G_1") (pintype "bidirectional"))
      (node (ref "R3") (pin "2") (pinfunction "2_2") (pintype "passive"))
      (node (ref "R5") (pin "2") (pinfunction "2_2") (pintype "passive"))
    )
    (net (code "32") (name "Net-(IC3-D)") (class "Default")
      (node (ref "C5") (pin "2") (pinfunction "2_2") (pintype "passive"))
      (node (ref "D2") (pin "A") (pinfunction "A_A") (pintype "passive"))
      (node (ref "IC3") (pin "4") (pinfunction "D_4") (pintype "bidirectional"))
      (node (ref "X2") (pin "1") (pinfunction "1_1") (pintype "passive"))
    )
    (net (code "33") (name "Net-(IC3-G)") (class "Default")
      (node (ref "IC3") (pin "1") (pinfunction "G_1") (pintype "bidirectional"))
      (node (ref "R8") (pin "2") (pinfunction "2_2") (pintype "passive"))
      (node (ref "R9") (pin "2") (pinfunction "2_2") (pintype "passive"))
    )
    (net (code "34") (name "Net-(IC4-D)") (class "Default")
      (node (ref "C7") (pin "2") (pinfunction "2_2") (pintype "passive"))
      (node (ref "D3") (pin "A") (pinfunction "A_A") (pintype "passive"))
      (node (ref "IC4") (pin "4") (pinfunction "D_4") (pintype "bidirectional"))
      (node (ref "X3") (pin "1") (pinfunction "1_1") (pintype "passive"))
    )
    (net (code "35") (name "Net-(IC4-G)") (class "Default")
      (node (ref "IC4") (pin "1") (pinfunction "G_1") (pintype "bidirectional"))
      (node (ref "R31") (pin "2") (pinfunction "2_2") (pintype "passive"))
      (node (ref "R32") (pin "2") (pinfunction "2_2") (pintype "passive"))
    )
    (net (code "36") (name "Net-(IC5-D)") (class "Default")
      (node (ref "C9") (pin "2") (pinfunction "2_2") (pintype "passive"))
      (node (ref "D4") (pin "A") (pinfunction "A_A") (pintype "passive"))
      (node (ref "IC5") (pin "4") (pinfunction "D_4") (pintype "bidirectional"))
      (node (ref "X4") (pin "1") (pinfunction "1_1") (pintype "passive"))
    )
    (net (code "37") (name "Net-(IC5-G)") (class "Default")
      (node (ref "IC5") (pin "1") (pinfunction "G_1") (pintype "bidirectional"))
      (node (ref "R35") (pin "2") (pinfunction "2_2") (pintype "passive"))
      (node (ref "R36") (pin "2") (pinfunction "2_2") (pintype "passive"))
    )
    (net (code "38") (name "Net-(IC6-D)") (class "Default")
      (node (ref "C23") (pin "2") (pinfunction "2_2") (pintype "passive"))
      (node (ref "D5") (pin "A") (pinfunction "A_A") (pintype "passive"))
      (node (ref "IC6") (pin "4") (pinfunction "D_4") (pintype "bidirectional"))
      (node (ref "X5") (pin "1") (pinfunction "1_1") (pintype "passive"))
    )
    (net (code "39") (name "Net-(IC6-G)") (class "Default")
      (node (ref "IC6") (pin "1") (pinfunction "G_1") (pintype "bidirectional"))
      (node (ref "R39") (pin "2") (pinfunction "2_2") (pintype "passive"))
      (node (ref "R40") (pin "2") (pinfunction "2_2") (pintype "passive"))
    )
    (net (code "40") (name "Net-(IC7-D)") (class "Default")
      (node (ref "C13") (pin "2") (pinfunction "2_2") (pintype "passive"))
      (node (ref "D6") (pin "A") (pinfunction "A_A") (pintype "passive"))
      (node (ref "IC7") (pin "4") (pinfunction "D_4") (pintype "bidirectional"))
      (node (ref "X6") (pin "1") (pinfunction "1_1") (pintype "passive"))
    )
    (net (code "41") (name "Net-(IC7-G)") (class "Default")
      (node (ref "IC7") (pin "1") (pinfunction "G_1") (pintype "bidirectional"))
      (node (ref "R43") (pin "2") (pinfunction "2_2") (pintype "passive"))
      (node (ref "R44") (pin "2") (pinfunction "2_2") (pintype "passive"))
    )
    (net (code "42") (name "Net-(L1-1)") (class "Default")
      (node (ref "D8") (pin "C") (pinfunction "C_C") (pintype "passive"))
      (node (ref "L1") (pin "P$1") (pinfunction "1_P$1") (pintype "passive"))
      (node (ref "U6") (pin "2") (pinfunction "SWE_2") (pintype "passive"))
    )
    (net (code "43") (name "Net-(Q2-ANODE)") (class "Default")
      (node (ref "Q2") (pin "1") (pinfunction "ANODE_1") (pintype "bidirectional"))
      (node (ref "R27") (pin "2") (pinfunction "2_2") (pintype "passive"))
    )
    (net (code "44") (name "Net-(Q2-COLLECTOR)") (class "Default")
      (node (ref "Q2") (pin "4") (pinfunction "COLLECTOR_4") (pintype "bidirectional"))
      (node (ref "R1") (pin "1") (pinfunction "1_1") (pintype "passive"))
      (node (ref "R28") (pin "1") (pinfunction "1_1") (pintype "passive"))
    )
    (net (code "45") (name "Net-(Q4-ANODE)") (class "Default")
      (node (ref "Q4") (pin "1") (pinfunction "ANODE_1") (pintype "bidirectional"))
      (node (ref "R6") (pin "2") (pinfunction "2_2") (pintype "passive"))
    )
    (net (code "46") (name "Net-(Q4-COLLECTOR)") (class "Default")
      (node (ref "Q4") (pin "4") (pinfunction "COLLECTOR_4") (pintype "bidirectional"))
      (node (ref "R3") (pin "1") (pinfunction "1_1") (pintype "passive"))
      (node (ref "R7") (pin "1") (pinfunction "1_1") (pintype "passive"))
    )
    (net (code "47") (name "Net-(Q6-ANODE)") (class "Default")
      (node (ref "Q6") (pin "1") (pinfunction "ANODE_1") (pintype "bidirectional"))
      (node (ref "R29") (pin "2") (pinfunction "2_2") (pintype "passive"))
    )
    (net (code "48") (name "Net-(Q6-COLLECTOR)") (class "Default")
      (node (ref "Q6") (pin "4") (pinfunction "COLLECTOR_4") (pintype "bidirectional"))
      (node (ref "R30") (pin "1") (pinfunction "1_1") (pintype "passive"))
      (node (ref "R8") (pin "1") (pinfunction "1_1") (pintype "passive"))
    )
    (net (code "49") (name "Net-(Q8-ANODE)") (class "Default")
      (node (ref "Q8") (pin "1") (pinfunction "ANODE_1") (pintype "bidirectional"))
      (node (ref "R33") (pin "2") (pinfunction "2_2") (pintype "passive"))
    )
    (net (code "50") (name "Net-(Q8-COLLECTOR)") (class "Default")
      (node (ref "Q8") (pin "4") (pinfunction "COLLECTOR_4") (pintype "bidirectional"))
      (node (ref "R31") (pin "1") (pinfunction "1_1") (pintype "passive"))
      (node (ref "R34") (pin "1") (pinfunction "1_1") (pintype "passive"))
    )
    (net (code "51") (name "Net-(Q10-ANODE)") (class "Default")
      (node (ref "Q10") (pin "1") (pinfunction "ANODE_1") (pintype "bidirectional"))
      (node (ref "R37") (pin "2") (pinfunction "2_2") (pintype "passive"))
    )
    (net (code "52") (name "Net-(Q10-COLLECTOR)") (class "Default")
      (node (ref "Q10") (pin "4") (pinfunction "COLLECTOR_4") (pintype "bidirectional"))
      (node (ref "R35") (pin "1") (pinfunction "1_1") (pintype "passive"))
      (node (ref "R38") (pin "1") (pinfunction "1_1") (pintype "passive"))
    )
    (net (code "53") (name "Net-(Q12-ANODE)") (class "Default")
      (node (ref "Q12") (pin "1") (pinfunction "ANODE_1") (pintype "bidirectional"))
      (node (ref "R41") (pin "2") (pinfunction "2_2") (pintype "passive"))
    )
    (net (code "54") (name "Net-(Q12-COLLECTOR)") (class "Default")
      (node (ref "Q12") (pin "4") (pinfunction "COLLECTOR_4") (pintype "bidirectional"))
      (node (ref "R39") (pin "1") (pinfunction "1_1") (pintype "passive"))
      (node (ref "R42") (pin "1") (pinfunction "1_1") (pintype "passive"))
    )
    (net (code "55") (name "Net-(Q14-ANODE)") (class "Default")
      (node (ref "Q14") (pin "1") (pinfunction "ANODE_1") (pintype "bidirectional"))
      (node (ref "R45") (pin "2") (pinfunction "2_2") (pintype "passive"))
    )
    (net (code "56") (name "Net-(Q14-COLLECTOR)") (class "Default")
      (node (ref "Q14") (pin "4") (pinfunction "COLLECTOR_4") (pintype "bidirectional"))
      (node (ref "R43") (pin "1") (pinfunction "1_1") (pintype "passive"))
      (node (ref "R46") (pin "1") (pinfunction "1_1") (pintype "passive"))
    )
    (net (code "57") (name "Net-(SW1-1)") (class "Default")
      (node (ref "R17") (pin "1") (pinfunction "1_1") (pintype "passive"))
      (node (ref "SW1") (pin "P$1") (pinfunction "1_P$1") (pintype "bidirectional"))
    )
    (net (code "58") (name "Net-(U1-OSC_IN)") (class "Default")
      (node (ref "U$6") (pin "1") (pinfunction "1_1") (pintype "passive"))
      (node (ref "U1") (pin "5") (pinfunction "OSC_IN_5") (pintype "input"))
    )
    (net (code "59") (name "Net-(U1-OSC_OUT)") (class "Default")
      (node (ref "U$6") (pin "3") (pinfunction "3_3") (pintype "passive"))
      (node (ref "U1") (pin "6") (pinfunction "OSC_OUT_6") (pintype "output"))
    )
    (net (code "60") (name "Net-(U6-DC)") (class "Default")
      (node (ref "R23") (pin "2") (pinfunction "2_2") (pintype "passive"))
      (node (ref "U6") (pin "1") (pinfunction "SWC_1") (pintype "passive"))
      (node (ref "U6") (pin "7") (pinfunction "IS_7") (pintype "passive"))
      (node (ref "U6") (pin "8") (pinfunction "DC_8") (pintype "passive"))
    )
    (net (code "61") (name "Net-(U6-FB)") (class "Default")
      (node (ref "R21") (pin "1") (pinfunction "1_1") (pintype "passive"))
      (node (ref "R22") (pin "2") (pinfunction "2_2") (pintype "passive"))
      (node (ref "U6") (pin "5") (pinfunction "FB_5") (pintype "passive"))
    )
    (net (code "62") (name "Net-(U6-TC)") (class "Default")
      (node (ref "C15") (pin "1") (pinfunction "1_1") (pintype "passive"))
      (node (ref "U6") (pin "3") (pinfunction "TC_3") (pintype "passive"))
    )
    (net (code "63") (name "SOLV0") (class "Default")
      (node (ref "R27") (pin "1") (pinfunction "1_1") (pintype "passive"))
      (node (ref "U1") (pin "21") (pinfunction "PB10_21") (pintype "bidirectional"))
    )
    (net (code "64") (name "SOLV1") (class "Default")
      (node (ref "R6") (pin "1") (pinfunction "1_1") (pintype "passive"))
      (node (ref "U1") (pin "22") (pinfunction "PB11_22") (pintype "bidirectional"))
    )
    (net (code "65") (name "SOLV2") (class "Default")
      (node (ref "R29") (pin "1") (pinfunction "1_1") (pintype "passive"))
      (node (ref "U1") (pin "25") (pinfunction "PB12_25") (pintype "bidirectional"))
    )
    (net (code "66") (name "SOLV3") (class "Default")
      (node (ref "R33") (pin "1") (pinfunction "1_1") (pintype "passive"))
      (node (ref "U1") (pin "26") (pinfunction "PB13_26") (pintype "bidirectional"))
    )
    (net (code "67") (name "SOLV4") (class "Default")
      (node (ref "R37") (pin "1") (pinfunction "1_1") (pintype "passive"))
      (node (ref "U1") (pin "27") (pinfunction "PB14_27") (pintype "bidirectional"))
    )
    (net (code "68") (name "SOLV5") (class "Default")
      (node (ref "R41") (pin "1") (pinfunction "1_1") (pintype "passive"))
      (node (ref "U1") (pin "28") (pinfunction "PB15_28") (pintype "bidirectional"))
    )
    (net (code "69") (name "SOLV6") (class "Default")
      (node (ref "R45") (pin "1") (pinfunction "1_1") (pintype "passive"))
      (node (ref "U1") (pin "29") (pinfunction "PA8_29") (pintype "bidirectional"))
    )
    (net (code "70") (name "SOLV7") (class "Default")
      (node (ref "U1") (pin "30") (pinfunction "PA9_30") (pintype "bidirectional"))
    )
    (net (code "71") (name "SOLV8") (class "Default")
      (node (ref "U1") (pin "41") (pinfunction "PB5_41") (pintype "bidirectional"))
    )
    (net (code "72") (name "SWCLK") (class "Default")
      (node (ref "JP1") (pin "4") (pinfunction "4_4") (pintype "passive"))
      (node (ref "U1") (pin "37") (pinfunction "PA14-JTCK-SWCLK_37") (pintype "bidirectional"))
    )
    (net (code "73") (name "SWDIO") (class "Default")
      (node (ref "JP1") (pin "6") (pinfunction "6_6") (pintype "passive"))
      (node (ref "U1") (pin "34") (pinfunction "PA13-JTMS-SWDIO_34") (pintype "bidirectional"))
    )
    (net (code "74") (name "UART_RX") (class "Default")
      (node (ref "JP1") (pin "1") (pinfunction "1_1") (pintype "passive"))
      (node (ref "U1") (pin "43") (pinfunction "PB7_43") (pintype "bidirectional"))
    )
    (net (code "75") (name "UART_TX") (class "Default")
      (node (ref "JP1") (pin "3") (pinfunction "3_3") (pintype "passive"))
      (node (ref "U1") (pin "42") (pinfunction "PB6_42") (pintype "bidirectional"))
    )
    (net (code "76") (name "VCC") (class "Default")
      (node (ref "C10") (pin "1") (pinfunction "1_1") (pintype "passive"))
      (node (ref "C12") (pin "1") (pinfunction "1_1") (pintype "passive"))
      (node (ref "C2") (pin "1") (pinfunction "1_1") (pintype "passive"))
      (node (ref "C21") (pin "1") (pinfunction "1_1") (pintype "passive"))
      (node (ref "C22") (pin "+") (pinfunction "+_+") (pintype "passive"))
      (node (ref "C4") (pin "1") (pinfunction "1_1") (pintype "passive"))
      (node (ref "C6") (pin "1") (pinfunction "1_1") (pintype "passive"))
      (node (ref "C8") (pin "1") (pinfunction "1_1") (pintype "passive"))
      (node (ref "D0") (pin "C") (pinfunction "C_C") (pintype "passive"))
      (node (ref "D1") (pin "C") (pinfunction "C_C") (pintype "passive"))
      (node (ref "D2") (pin "C") (pinfunction "C_C") (pintype "passive"))
      (node (ref "D3") (pin "C") (pinfunction "C_C") (pintype "passive"))
      (node (ref "D4") (pin "C") (pinfunction "C_C") (pintype "passive"))
      (node (ref "D5") (pin "C") (pinfunction "C_C") (pintype "passive"))
      (node (ref "D6") (pin "C") (pinfunction "C_C") (pintype "passive"))
      (node (ref "J1") (pin "2") (pinfunction "2_2") (pintype "bidirectional"))
      (node (ref "R28") (pin "2") (pinfunction "2_2") (pintype "passive"))
      (node (ref "R30") (pin "2") (pinfunction "2_2") (pintype "passive"))
      (node (ref "R34") (pin "2") (pinfunction "2_2") (pintype "passive"))
      (node (ref "R38") (pin "2") (pinfunction "2_2") (pintype "passive"))
      (node (ref "R42") (pin "2") (pinfunction "2_2") (pintype "passive"))
      (node (ref "R46") (pin "2") (pinfunction "2_2") (pintype "passive"))
      (node (ref "R7") (pin "2") (pinfunction "2_2") (pintype "passive"))
      (node (ref "X0") (pin "2") (pinfunction "2_2") (pintype "passive"))
      (node (ref "X1") (pin "2") (pinfunction "2_2") (pintype "passive"))
      (node (ref "X2") (pin "2") (pinfunction "2_2") (pintype "passive"))
      (node (ref "X3") (pin "2") (pinfunction "2_2") (pintype "passive"))
      (node (ref "X4") (pin "2") (pinfunction "2_2") (pintype "passive"))
      (node (ref "X5") (pin "2") (pinfunction "2_2") (pintype "passive"))
      (node (ref "X6") (pin "2") (pinfunction "2_2") (pintype "passive"))
    )
    (net (code "77") (name "unconnected-(U1-PA0-WKUP-Pad10)") (class "Default")
      (node (ref "U1") (pin "10") (pinfunction "PA0-WKUP_10") (pintype "bidirectional"))
    )
    (net (code "78") (name "unconnected-(U1-PA1-Pad11)") (class "Default")
      (node (ref "U1") (pin "11") (pinfunction "PA1_11") (pintype "bidirectional"))
    )
    (net (code "79") (name "unconnected-(U1-PA2-Pad12)") (class "Default")
      (node (ref "U1") (pin "12") (pinfunction "PA2_12") (pintype "bidirectional"))
    )
    (net (code "80") (name "unconnected-(U1-PA3-Pad13)") (class "Default")
      (node (ref "U1") (pin "13") (pinfunction "PA3_13") (pintype "bidirectional"))
    )
    (net (code "81") (name "unconnected-(U1-PA4-Pad14)") (class "Default")
      (node (ref "U1") (pin "14") (pinfunction "PA4_14") (pintype "bidirectional"))
    )
    (net (code "82") (name "unconnected-(U1-PA5-Pad15)") (class "Default")
      (node (ref "U1") (pin "15") (pinfunction "PA5_15") (pintype "bidirectional"))
    )
    (net (code "83") (name "unconnected-(U1-PA10-Pad31)") (class "Default")
      (node (ref "U1") (pin "31") (pinfunction "PA10_31") (pintype "bidirectional"))
    )
    (net (code "84") (name "unconnected-(U1-PA11-Pad32)") (class "Default")
      (node (ref "U1") (pin "32") (pinfunction "PA11_32") (pintype "bidirectional"))
    )
    (net (code "85") (name "unconnected-(U1-PA12-Pad33)") (class "Default")
      (node (ref "U1") (pin "33") (pinfunction "PA12_33") (pintype "bidirectional"))
    )
    (net (code "86") (name "unconnected-(U1-PA15-JTDI-Pad38)") (class "Default")
      (node (ref "U1") (pin "38") (pinfunction "PA15-JTDI_38") (pintype "bidirectional"))
    )
    (net (code "87") (name "unconnected-(U1-PB1-Pad19)") (class "Default")
      (node (ref "U1") (pin "19") (pinfunction "PB1_19") (pintype "bidirectional"))
    )
    (net (code "88") (name "unconnected-(U1-PB2-BOOT1-Pad20)") (class "Default")
      (node (ref "U1") (pin "20") (pinfunction "PB2-BOOT1_20") (pintype "bidirectional"))
    )
    (net (code "89") (name "unconnected-(U1-PB3-JTDO-Pad39)") (class "Default")
      (node (ref "U1") (pin "39") (pinfunction "PB3-JTDO_39") (pintype "bidirectional"))
    )
    (net (code "90") (name "unconnected-(U1-PB4-JNTRST-Pad40)") (class "Default")
      (node (ref "U1") (pin "40") (pinfunction "PB4-JNTRST_40") (pintype "bidirectional"))
    )
    (net (code "91") (name "unconnected-(U1-PC15-OSC32_OUT-Pad4)") (class "Default")
      (node (ref "U1") (pin "4") (pinfunction "PC15-OSC32_OUT_4") (pintype "bidirectional"))
    )
    (net (code "92") (name "unconnected-(U1-VBAT-Pad1)") (class "Default")
      (node (ref "U1") (pin "1") (pinfunction "VBAT_1") (pintype "passive"))
    )
    (net (code "93") (name "~{EMS}") (class "Default")
      (node (ref "R18") (pin "1") (pinfunction "1_1") (pintype "passive"))
      (node (ref "U1") (pin "2") (pinfunction "PC13-TAMPER-RTC_2") (pintype "bidirectional"))
    )
    (net (code "94") (name "~{RESET}") (class "Default")
      (node (ref "C20") (pin "2") (pinfunction "2_2") (pintype "passive"))
      (node (ref "R16") (pin "2") (pinfunction "2_2") (pintype "passive"))
      (node (ref "SW1") (pin "P$2") (pinfunction "2_P$2") (pintype "bidirectional"))
      (node (ref "U1") (pin "7") (pinfunction "NRST_7") (pintype "bidirectional"))
    )
  )
)
